# Schematic_v24.net
KiCad netlist of a schematic drawn in EAGLE
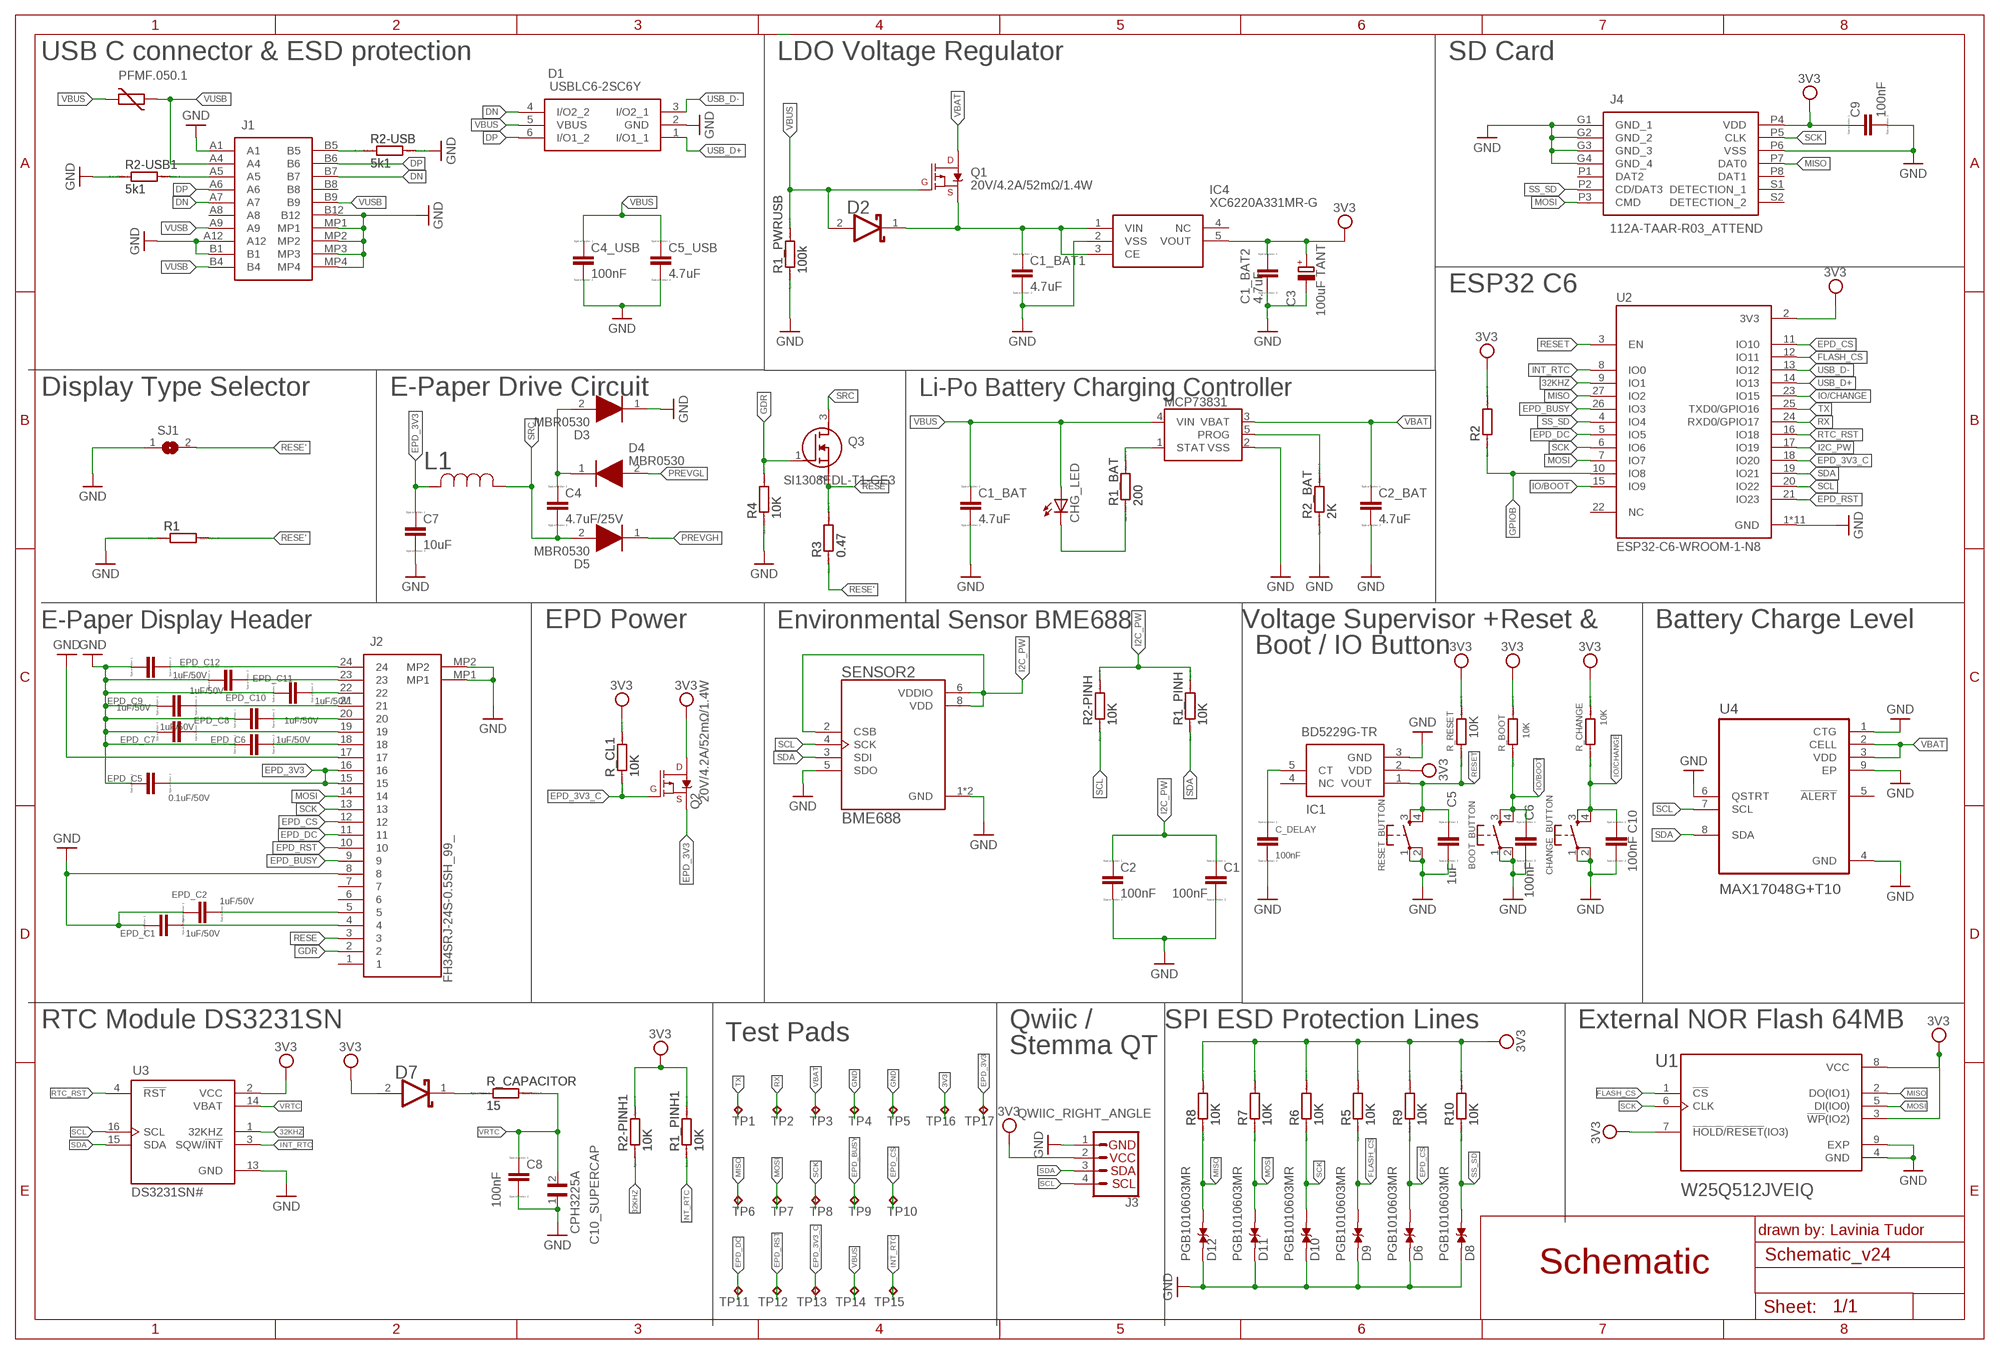
[diagram p0: schematic, sheet 1]

(export (version "E")
  (design (tool "Eeschema 10.0.6"))
  (components
    (comp (ref "BOOT_BUTTON")
      (value "BUTTON_CUSYOMV1")
      (footprint "eagle-import:MYBUTTON")
      (libsource (lib "eagle-import") (part "BUTTON_CUSYOMV1"))
    )
    (comp (ref "C1")
      (value "100nF")
      (footprint "eagle-import:ESP32_WROVER_EAGLE-LTSPICE_C0402")
      (libsource (lib "eagle-import") (part "ESP32_WROVER_EAGLE-LTSPICE_CC0402"))
    )
    (comp (ref "C1_BAT")
      (value "4.7uF")
      (footprint "eagle-import:ESP32_WROVER_EAGLE-LTSPICE_C0402")
      (libsource (lib "eagle-import") (part "ESP32_WROVER_EAGLE-LTSPICE_CC0402"))
    )
    (comp (ref "C1_BAT1")
      (value "4.7uF")
      (footprint "eagle-import:ESP32_WROVER_EAGLE-LTSPICE_C0402")
      (libsource (lib "eagle-import") (part "ESP32_WROVER_EAGLE-LTSPICE_CC0402"))
    )
    (comp (ref "C1_BAT2")
      (value "4.7uF")
      (footprint "eagle-import:ESP32_WROVER_EAGLE-LTSPICE_C0402")
      (libsource (lib "eagle-import") (part "ESP32_WROVER_EAGLE-LTSPICE_CC0402"))
    )
    (comp (ref "C2")
      (value "100nF")
      (footprint "eagle-import:ESP32_WROVER_EAGLE-LTSPICE_C0402")
      (libsource (lib "eagle-import") (part "ESP32_WROVER_EAGLE-LTSPICE_CC0402"))
    )
    (comp (ref "C2_BAT")
      (value "4.7uF")
      (footprint "eagle-import:ESP32_WROVER_EAGLE-LTSPICE_C0402")
      (libsource (lib "eagle-import") (part "ESP32_WROVER_EAGLE-LTSPICE_CC0402"))
    )
    (comp (ref "C3")
      (value "100uF TANT")
      (footprint "eagle-import:RCL_CT3528")
      (libsource (lib "eagle-import") (part "RCL_CPOL-EUCT3528"))
    )
    (comp (ref "C4")
      (value "4.7uF/25V")
      (footprint "eagle-import:ESP32_WROVER_EAGLE-LTSPICE_C0402")
      (libsource (lib "eagle-import") (part "ESP32_WROVER_EAGLE-LTSPICE_CC0402"))
    )
    (comp (ref "C4_USB")
      (value "100nF")
      (footprint "eagle-import:EAGLE-LTSPICE_C0402")
      (libsource (lib "eagle-import") (part "EAGLE-LTSPICE_CC0402"))
    )
    (comp (ref "C5")
      (value "1uF")
      (footprint "eagle-import:ESP32_WROVER_EAGLE-LTSPICE_C0402")
      (libsource (lib "eagle-import") (part "ESP32_WROVER_EAGLE-LTSPICE_CC0402"))
    )
    (comp (ref "C5_USB")
      (value "4.7uF")
      (footprint "eagle-import:EAGLE-LTSPICE_C0402")
      (libsource (lib "eagle-import") (part "EAGLE-LTSPICE_CC0402"))
    )
    (comp (ref "C6")
      (value "100nF")
      (footprint "eagle-import:ESP32_WROVER_EAGLE-LTSPICE_C0402")
      (libsource (lib "eagle-import") (part "ESP32_WROVER_EAGLE-LTSPICE_CC0402"))
    )
    (comp (ref "C7")
      (value "10uF")
      (footprint "eagle-import:ESP32_WROVER_EAGLE-LTSPICE_C0402")
      (libsource (lib "eagle-import") (part "ESP32_WROVER_EAGLE-LTSPICE_CC0402"))
    )
    (comp (ref "C8")
      (value "100nF")
      (footprint "eagle-import:ESP32_WROVER_EAGLE-LTSPICE_C0402")
      (libsource (lib "eagle-import") (part "ESP32_WROVER_EAGLE-LTSPICE_CC0402"))
    )
    (comp (ref "C9")
      (value "100nF")
      (footprint "eagle-import:EAGLE-LTSPICE_C0402")
      (libsource (lib "eagle-import") (part "EAGLE-LTSPICE_CC0402"))
    )
    (comp (ref "C10")
      (value "100nF")
      (footprint "eagle-import:ESP32_WROVER_EAGLE-LTSPICE_C0402")
      (libsource (lib "eagle-import") (part "ESP32_WROVER_EAGLE-LTSPICE_CC0402"))
    )
    (comp (ref "C10_SUPERCAP")
      (value "CPH3225A")
      (footprint "eagle-import:CAPCP3225X100N")
      (fields (field (name "MF") "Seiko Instruments"))
      (libsource (lib "eagle-import") (part "CPH3225A"))
    )
    (comp (ref "CHANGE_BUTTON")
      (value "BUTTON_CUSYOMV1")
      (footprint "eagle-import:MYBUTTON")
      (libsource (lib "eagle-import") (part "BUTTON_CUSYOMV1"))
    )
    (comp (ref "CHG_LED")
      (value "ADAFRUIT_LEDCHIP-LED0603")
      (footprint "eagle-import:ADAFRUIT_CHIP-LED0603")
      (libsource (lib "eagle-import") (part "ADAFRUIT_LEDCHIP-LED0603"))
    )
    (comp (ref "C_DELAY")
      (value "100nF")
      (footprint "eagle-import:ESP32_WROVER_EAGLE-LTSPICE_C0402")
      (libsource (lib "eagle-import") (part "ESP32_WROVER_EAGLE-LTSPICE_CC0402"))
    )
    (comp (ref "D1")
      (value "USBLC6-2SC6Y")
      (footprint "eagle-import:SOT95P280X145-6N")
      (fields (field (name "MF") "STMicroelectronics"))
      (libsource (lib "eagle-import") (part "USBLC6-2SC6Y"))
    )
    (comp (ref "D2")
      (value "ESP32_WROVER_AVX---SD0805S020S1R0_AVX_SD0805S020S1R0_0_0AVX_SD0805S020S1R0_0_0")
      (footprint "eagle-import:ESP32_WROVER_AVX---SD0805S020S1R0_AVX_SD0805S020S1R0_0")
      (fields
        (field (name "DIGIKEY_PART_NUMBER") "478-7800-1-ND")
        (field (name "MF") "AVX")
        (field (name "MOUSER_PART_NUMBER") "581-SD0805S020S1R0")
      )
      (libsource (lib "eagle-import") (part "ESP32_WROVER_AVX---SD0805S020S1R0_AVX_SD0805S020S1R0_0_0AVX_SD0805S020S1R0_0_0"))
    )
    (comp (ref "D3")
      (value "MBR0530")
      (footprint "eagle-import:SOD3716X135N")
      (fields (field (name "MF") "ON Semiconductor"))
      (libsource (lib "eagle-import") (part "MBR0530"))
    )
    (comp (ref "D4")
      (value "MBR0530")
      (footprint "eagle-import:SOD3716X135N")
      (fields (field (name "MF") "ON Semiconductor"))
      (libsource (lib "eagle-import") (part "MBR0530"))
    )
    (comp (ref "D5")
      (value "MBR0530")
      (footprint "eagle-import:SOD3716X135N")
      (fields (field (name "MF") "ON Semiconductor"))
      (libsource (lib "eagle-import") (part "MBR0530"))
    )
    (comp (ref "D6")
      (value "PGB1010603MR")
      (footprint "eagle-import:DIOC1608X36N")
      (fields (field (name "MF") "Littelfuse Inc."))
      (libsource (lib "eagle-import") (part "PGB1010603MR"))
    )
    (comp (ref "D7")
      (value "ESP32_WROVER_AVX---SD0805S020S1R0_AVX_SD0805S020S1R0_0_0AVX_SD0805S020S1R0_0_0")
      (footprint "eagle-import:ESP32_WROVER_AVX---SD0805S020S1R0_AVX_SD0805S020S1R0_0")
      (fields
        (field (name "DIGIKEY_PART_NUMBER") "478-7800-1-ND")
        (field (name "MF") "AVX")
        (field (name "MOUSER_PART_NUMBER") "581-SD0805S020S1R0")
      )
      (libsource (lib "eagle-import") (part "ESP32_WROVER_AVX---SD0805S020S1R0_AVX_SD0805S020S1R0_0_0AVX_SD0805S020S1R0_0_0"))
    )
    (comp (ref "D8")
      (value "PGB1010603MR")
      (footprint "eagle-import:DIOC1608X36N")
      (fields (field (name "MF") "Littelfuse Inc."))
      (libsource (lib "eagle-import") (part "PGB1010603MR"))
    )
    (comp (ref "D9")
      (value "PGB1010603MR")
      (footprint "eagle-import:DIOC1608X36N")
      (fields (field (name "MF") "Littelfuse Inc."))
      (libsource (lib "eagle-import") (part "PGB1010603MR"))
    )
    (comp (ref "D10")
      (value "PGB1010603MR")
      (footprint "eagle-import:DIOC1608X36N")
      (fields (field (name "MF") "Littelfuse Inc."))
      (libsource (lib "eagle-import") (part "PGB1010603MR"))
    )
    (comp (ref "D11")
      (value "PGB1010603MR")
      (footprint "eagle-import:DIOC1608X36N")
      (fields (field (name "MF") "Littelfuse Inc."))
      (libsource (lib "eagle-import") (part "PGB1010603MR"))
    )
    (comp (ref "D12")
      (value "PGB1010603MR")
      (footprint "eagle-import:DIOC1608X36N")
      (fields (field (name "MF") "Littelfuse Inc."))
      (libsource (lib "eagle-import") (part "PGB1010603MR"))
    )
    (comp (ref "EPD_C1")
      (value "1uF/50V")
      (footprint "eagle-import:ESP32_WROVER_EAGLE-LTSPICE_C0402")
      (libsource (lib "eagle-import") (part "ESP32_WROVER_EAGLE-LTSPICE_CC0402"))
    )
    (comp (ref "EPD_C2")
      (value "1uF/50V")
      (footprint "eagle-import:ESP32_WROVER_EAGLE-LTSPICE_C0402")
      (libsource (lib "eagle-import") (part "ESP32_WROVER_EAGLE-LTSPICE_CC0402"))
    )
    (comp (ref "EPD_C5")
      (value "0.1uF/50V")
      (footprint "eagle-import:ESP32_WROVER_EAGLE-LTSPICE_C0402")
      (libsource (lib "eagle-import") (part "ESP32_WROVER_EAGLE-LTSPICE_CC0402"))
    )
    (comp (ref "EPD_C6")
      (value "1uF/50V")
      (footprint "eagle-import:ESP32_WROVER_EAGLE-LTSPICE_C0402")
      (libsource (lib "eagle-import") (part "ESP32_WROVER_EAGLE-LTSPICE_CC0402"))
    )
    (comp (ref "EPD_C7")
      (value "1uF/50V")
      (footprint "eagle-import:ESP32_WROVER_EAGLE-LTSPICE_C0402")
      (libsource (lib "eagle-import") (part "ESP32_WROVER_EAGLE-LTSPICE_CC0402"))
    )
    (comp (ref "EPD_C8")
      (value "1uF/50V")
      (footprint "eagle-import:ESP32_WROVER_EAGLE-LTSPICE_C0402")
      (libsource (lib "eagle-import") (part "ESP32_WROVER_EAGLE-LTSPICE_CC0402"))
    )
    (comp (ref "EPD_C9")
      (value "1uF/50V")
      (footprint "eagle-import:ESP32_WROVER_EAGLE-LTSPICE_C0402")
      (libsource (lib "eagle-import") (part "ESP32_WROVER_EAGLE-LTSPICE_CC0402"))
    )
    (comp (ref "EPD_C10")
      (value "1uF/50V")
      (footprint "eagle-import:ESP32_WROVER_EAGLE-LTSPICE_C0402")
      (libsource (lib "eagle-import") (part "ESP32_WROVER_EAGLE-LTSPICE_CC0402"))
    )
    (comp (ref "EPD_C11")
      (value "1uF/50V")
      (footprint "eagle-import:ESP32_WROVER_EAGLE-LTSPICE_C0402")
      (libsource (lib "eagle-import") (part "ESP32_WROVER_EAGLE-LTSPICE_CC0402"))
    )
    (comp (ref "EPD_C12")
      (value "1uF/50V")
      (footprint "eagle-import:ESP32_WROVER_EAGLE-LTSPICE_C0402")
      (libsource (lib "eagle-import") (part "ESP32_WROVER_EAGLE-LTSPICE_CC0402"))
    )
    (comp (ref "IC1")
      (value "BD5229G-TR")
      (footprint "eagle-import:SOT95P280X125-5N")
      (fields (field (name "MOUSER_PART_NUMBER") "755-BD5229G-TR"))
      (libsource (lib "eagle-import") (part "BD5229G-TR"))
    )
    (comp (ref "IC4")
      (value "XC6220A331MR-G")
      (footprint "eagle-import:SOT95P280X120-5N")
      (fields (field (name "MOUSER_PART_NUMBER") "865-XC6220A331MR-G"))
      (libsource (lib "eagle-import") (part "XC6220A331MR-G"))
    )
    (comp (ref "J1")
      (value "SAMACSYS_PARTS_USB4110-GF-A")
      (footprint "eagle-import:SAMACSYS_PARTS_USB4110GFA")
      (fields
        (field (name "MANUFACTURER_PART_NUMBER") "USB4110-GF-A")
        (field (name "MOUSER_PART_NUMBER") "640-USB4110-GF-A")
      )
      (libsource (lib "eagle-import") (part "SAMACSYS_PARTS_USB4110-GF-A"))
    )
    (comp (ref "J2")
      (value "FH34SRJ-24S-0.5SH_99_")
      (footprint "eagle-import:FH34SRJ24S05SH99")
      (fields
        (field (name "MANUFACTURER_PART_NUMBER") "FH34SRJ-24S-0.5SH(99)")
        (field (name "MOUSER_PART_NUMBER") "798-FH34SRJ24S05SH99")
      )
      (libsource (lib "eagle-import") (part "FH34SRJ-24S-0.5SH_99_"))
    )
    (comp (ref "J3")
      (value "QWIIC_RIGHT_ANGLE")
      (footprint "eagle-import:JST04_1MM_RA")
      (libsource (lib "eagle-import") (part "QWIIC_CONNECTORJS-1MM"))
    )
    (comp (ref "J4")
      (value "112A-TAAR-R03_ATTEND")
      (footprint "eagle-import:112ATAARR03ATTEND")
      (fields (field (name "MANUFACTURER_PART_NUMBER") "112A-TAAR-R03 ATTEND"))
      (libsource (lib "eagle-import") (part "112A-TAAR-R03_ATTEND"))
    )
    (comp (ref "L1")
      (value "744043680IND_4828-WE-TPC_WRE")
      (footprint "eagle-import:IND_4828-WE-TPC_WRE")
      (fields
        (field (name "MANUFACTURER_PART_NUMBER") "744043680")
        (field (name "COPYRIGHT") "Copyright (C) 2024 Ultra Librarian. All rights reserved.")
      )
      (libsource (lib "eagle-import") (part "744043680IND_4828-WE-TPC_WRE"))
    )
    (comp (ref "MCP73831")
      (value "ESP32_WROVER_SPARKFUN-IC-POWER_MCP73831")
      (footprint "eagle-import:ESP32_WROVER_SPARKFUN-IC-POWER_SOT23-5")
      (libsource (lib "eagle-import") (part "ESP32_WROVER_SPARKFUN-IC-POWER_MCP73831"))
    )
    (comp (ref "PFMF.050.1")
      (value "ESP32C6_VARISTORCN1812")
      (footprint "eagle-import:ESP32C6_VARISTOR_CT_CN1812")
      (libsource (lib "eagle-import") (part "ESP32C6_VARISTORCN1812"))
    )
    (comp (ref "Q1")
      (value "20V/4.2A/52mΩ/1.4W")
      (footprint "eagle-import:ESP32_WROVER_SPARKFUN-DISCRETESEMI_SOT23-3")
      (libsource (lib "eagle-import") (part "ESP32_WROVER_SPARKFUN-DISCRETESEMI_MOSFET_PCH-DMG2305UX-7"))
    )
    (comp (ref "Q2")
      (value "20V/4.2A/52mΩ/1.4W")
      (footprint "eagle-import:ESP32_WROVER_SPARKFUN-DISCRETESEMI_SOT23-3")
      (libsource (lib "eagle-import") (part "ESP32_WROVER_SPARKFUN-DISCRETESEMI_MOSFET_PCH-DMG2305UX-7"))
    )
    (comp (ref "Q3")
      (value "SI1308EDL-T1-GE3")
      (footprint "eagle-import:SOT65P210X110-3N")
      (fields (field (name "MF") "Vishay Siliconix"))
      (libsource (lib "eagle-import") (part "SI1308EDL-T1-GE3"))
    )
    (comp (ref "R1")
      (value "ESP32_WROVER_EAGLE-LTSPICE_RR0402")
      (footprint "eagle-import:ESP32_WROVER_EAGLE-LTSPICE_R0402")
      (libsource (lib "eagle-import") (part "ESP32_WROVER_EAGLE-LTSPICE_RR0402"))
    )
    (comp (ref "R1_BAT")
      (value "200")
      (footprint "eagle-import:ESP32_WROVER_EAGLE-LTSPICE_R0402")
      (libsource (lib "eagle-import") (part "ESP32_WROVER_EAGLE-LTSPICE_RR0402"))
    )
    (comp (ref "R1_PINH")
      (value "10K")
      (footprint "eagle-import:ESP32_WROVER_EAGLE-LTSPICE_R0402")
      (libsource (lib "eagle-import") (part "ESP32_WROVER_EAGLE-LTSPICE_RR0402"))
    )
    (comp (ref "R1_PINH1")
      (value "10K")
      (footprint "eagle-import:ESP32_WROVER_EAGLE-LTSPICE_R0402")
      (libsource (lib "eagle-import") (part "ESP32_WROVER_EAGLE-LTSPICE_RR0402"))
    )
    (comp (ref "R1_PWRUSB")
      (value "100k")
      (footprint "eagle-import:ESP32_WROVER_EAGLE-LTSPICE_R0402")
      (libsource (lib "eagle-import") (part "ESP32_WROVER_EAGLE-LTSPICE_RR0402"))
    )
    (comp (ref "R2")
      (value "ESP32_WROVER_EAGLE-LTSPICE_RR0402")
      (footprint "eagle-import:ESP32_WROVER_EAGLE-LTSPICE_R0402")
      (libsource (lib "eagle-import") (part "ESP32_WROVER_EAGLE-LTSPICE_RR0402"))
    )
    (comp (ref "R2-PINH")
      (value "10K")
      (footprint "eagle-import:ESP32_WROVER_EAGLE-LTSPICE_R0402")
      (libsource (lib "eagle-import") (part "ESP32_WROVER_EAGLE-LTSPICE_RR0402"))
    )
    (comp (ref "R2-PINH1")
      (value "10K")
      (footprint "eagle-import:ESP32_WROVER_EAGLE-LTSPICE_R0402")
      (libsource (lib "eagle-import") (part "ESP32_WROVER_EAGLE-LTSPICE_RR0402"))
    )
    (comp (ref "R2-USB")
      (value "5k1")
      (footprint "eagle-import:ESP32_WROVER_EAGLE-LTSPICE_R0402")
      (libsource (lib "eagle-import") (part "ESP32_WROVER_EAGLE-LTSPICE_RR0402"))
    )
    (comp (ref "R2-USB1")
      (value "5k1")
      (footprint "eagle-import:ESP32_WROVER_EAGLE-LTSPICE_R0402")
      (libsource (lib "eagle-import") (part "ESP32_WROVER_EAGLE-LTSPICE_RR0402"))
    )
    (comp (ref "R2_BAT")
      (value "2K")
      (footprint "eagle-import:ESP32_WROVER_EAGLE-LTSPICE_R0402")
      (libsource (lib "eagle-import") (part "ESP32_WROVER_EAGLE-LTSPICE_RR0402"))
    )
    (comp (ref "R3")
      (value "0.47")
      (footprint "eagle-import:ESP32_WROVER_EAGLE-LTSPICE_R0402")
      (libsource (lib "eagle-import") (part "ESP32_WROVER_EAGLE-LTSPICE_RR0402"))
    )
    (comp (ref "R4")
      (value "10K")
      (footprint "eagle-import:ESP32_WROVER_EAGLE-LTSPICE_R0402")
      (libsource (lib "eagle-import") (part "ESP32_WROVER_EAGLE-LTSPICE_RR0402"))
    )
    (comp (ref "R5")
      (value "10K")
      (footprint "eagle-import:ESP32_WROVER_EAGLE-LTSPICE_R0402")
      (libsource (lib "eagle-import") (part "ESP32_WROVER_EAGLE-LTSPICE_RR0402"))
    )
    (comp (ref "R6")
      (value "10K")
      (footprint "eagle-import:ESP32_WROVER_EAGLE-LTSPICE_R0402")
      (libsource (lib "eagle-import") (part "ESP32_WROVER_EAGLE-LTSPICE_RR0402"))
    )
    (comp (ref "R7")
      (value "10K")
      (footprint "eagle-import:ESP32_WROVER_EAGLE-LTSPICE_R0402")
      (libsource (lib "eagle-import") (part "ESP32_WROVER_EAGLE-LTSPICE_RR0402"))
    )
    (comp (ref "R8")
      (value "10K")
      (footprint "eagle-import:ESP32_WROVER_EAGLE-LTSPICE_R0402")
      (libsource (lib "eagle-import") (part "ESP32_WROVER_EAGLE-LTSPICE_RR0402"))
    )
    (comp (ref "R9")
      (value "10K")
      (footprint "eagle-import:ESP32_WROVER_EAGLE-LTSPICE_R0402")
      (libsource (lib "eagle-import") (part "ESP32_WROVER_EAGLE-LTSPICE_RR0402"))
    )
    (comp (ref "R10")
      (value "10K")
      (footprint "eagle-import:ESP32_WROVER_EAGLE-LTSPICE_R0402")
      (libsource (lib "eagle-import") (part "ESP32_WROVER_EAGLE-LTSPICE_RR0402"))
    )
    (comp (ref "RESET_BUTTON")
      (value "BUTTON_CUSYOMV1")
      (footprint "eagle-import:MYBUTTON")
      (libsource (lib "eagle-import") (part "BUTTON_CUSYOMV1"))
    )
    (comp (ref "R_BOOT")
      (value "10K")
      (footprint "eagle-import:ESP32_WROVER_EAGLE-LTSPICE_R0402")
      (libsource (lib "eagle-import") (part "ESP32_WROVER_EAGLE-LTSPICE_RR0402"))
    )
    (comp (ref "R_CAPACITOR")
      (value "15")
      (footprint "eagle-import:ESP32_WROVER_EAGLE-LTSPICE_R0402")
      (libsource (lib "eagle-import") (part "ESP32_WROVER_EAGLE-LTSPICE_RR0402"))
    )
    (comp (ref "R_CHANGE")
      (value "10K")
      (footprint "eagle-import:ESP32_WROVER_EAGLE-LTSPICE_R0402")
      (libsource (lib "eagle-import") (part "ESP32_WROVER_EAGLE-LTSPICE_RR0402"))
    )
    (comp (ref "R_CL1")
      (value "10K")
      (footprint "eagle-import:ESP32_WROVER_EAGLE-LTSPICE_R0402")
      (libsource (lib "eagle-import") (part "ESP32_WROVER_EAGLE-LTSPICE_RR0402"))
    )
    (comp (ref "R_RESET")
      (value "10K")
      (footprint "eagle-import:ESP32_WROVER_EAGLE-LTSPICE_R0402")
      (libsource (lib "eagle-import") (part "ESP32_WROVER_EAGLE-LTSPICE_RR0402"))
    )
    (comp (ref "SENSOR2")
      (value "BME688")
      (footprint "eagle-import:ESP32_WROVER_BME680_PSON80P300X300X100-8N")
      (fields (field (name "MF") "Bosch Sensortec") (field (name "MP") "BME680"))
      (libsource (lib "eagle-import") (part "ESP32_WROVER_BME680_BME680"))
    )
    (comp (ref "SJ1") (value "SJ") (footprint "eagle-import:SJ") (libsource (lib "eagle-import") (part "SJ")))
    (comp (ref "TP1")
      (value "TPTP20R")
      (footprint "eagle-import:TP20R")
      (libsource (lib "eagle-import") (part "TPTP20R"))
    )
    (comp (ref "TP2")
      (value "TPTP20R")
      (footprint "eagle-import:TP20R")
      (libsource (lib "eagle-import") (part "TPTP20R"))
    )
    (comp (ref "TP3")
      (value "TPTP20R")
      (footprint "eagle-import:TP20R")
      (libsource (lib "eagle-import") (part "TPTP20R"))
    )
    (comp (ref "TP4")
      (value "TPTP20R")
      (footprint "eagle-import:TP20R")
      (libsource (lib "eagle-import") (part "TPTP20R"))
    )
    (comp (ref "TP5")
      (value "TPTP20R")
      (footprint "eagle-import:TP20R")
      (libsource (lib "eagle-import") (part "TPTP20R"))
    )
    (comp (ref "TP6")
      (value "TPTP20R")
      (footprint "eagle-import:TP20R")
      (libsource (lib "eagle-import") (part "TPTP20R"))
    )
    (comp (ref "TP7")
      (value "TPTP20R")
      (footprint "eagle-import:TP20R")
      (libsource (lib "eagle-import") (part "TPTP20R"))
    )
    (comp (ref "TP8")
      (value "TPTP20R")
      (footprint "eagle-import:TP20R")
      (libsource (lib "eagle-import") (part "TPTP20R"))
    )
    (comp (ref "TP9")
      (value "TPTP20R")
      (footprint "eagle-import:TP20R")
      (libsource (lib "eagle-import") (part "TPTP20R"))
    )
    (comp (ref "TP10")
      (value "TPTP20R")
      (footprint "eagle-import:TP20R")
      (libsource (lib "eagle-import") (part "TPTP20R"))
    )
    (comp (ref "TP11")
      (value "TPTP20R")
      (footprint "eagle-import:TP20R")
      (libsource (lib "eagle-import") (part "TPTP20R"))
    )
    (comp (ref "TP12")
      (value "TPTP20R")
      (footprint "eagle-import:TP20R")
      (libsource (lib "eagle-import") (part "TPTP20R"))
    )
    (comp (ref "TP13")
      (value "TPTP20R")
      (footprint "eagle-import:TP20R")
      (libsource (lib "eagle-import") (part "TPTP20R"))
    )
    (comp (ref "TP14")
      (value "TPTP20R")
      (footprint "eagle-import:TP20R")
      (libsource (lib "eagle-import") (part "TPTP20R"))
    )
    (comp (ref "TP15")
      (value "TPTP20R")
      (footprint "eagle-import:TP20R")
      (libsource (lib "eagle-import") (part "TPTP20R"))
    )
    (comp (ref "TP16")
      (value "TPTP20R")
      (footprint "eagle-import:TP20R")
      (libsource (lib "eagle-import") (part "TPTP20R"))
    )
    (comp (ref "TP17")
      (value "TPTP20R")
      (footprint "eagle-import:TP20R")
      (libsource (lib "eagle-import") (part "TPTP20R"))
    )
    (comp (ref "U1")
      (value "W25Q512JVEIQ")
      (footprint "eagle-import:SON127P600X800X80-9N")
      (fields (field (name "MF") "Winbond Electronics"))
      (libsource (lib "eagle-import") (part "W25Q512JVEIQ"))
    )
    (comp (ref "U2")
      (value "ESP32-C6-WROOM-1-N8")
      (footprint "eagle-import:XCVR_ESP32-C6-WROOM-1-N8")
      (fields (field (name "MF") "Espressif Systems"))
      (libsource (lib "eagle-import") (part "ESP32-C6-WROOM-1-N8"))
    )
    (comp (ref "U3")
      (value "DS3231SN#")
      (footprint "eagle-import:SOIC127P1032X265-16N")
      (fields (field (name "MF") "Analog Devices"))
      (libsource (lib "eagle-import") (part "DS3231SN#"))
    )
    (comp (ref "U4")
      (value "MAX17048G+T10")
      (footprint "eagle-import:SON50P200X200X80-9N")
      (fields (field (name "MF") "Analog Devices"))
      (libsource (lib "eagle-import") (part "MAX17048G+T10"))
    )
  )
  (nets
    (net (code "1") (name "3V3") (class "Default")
      (node (ref "C1_BAT2") (pin "1") (pinfunction "1_1") (pintype "passive"))
      (node (ref "C3") (pin "+") (pinfunction "+_+") (pintype "passive"))
      (node (ref "C9") (pin "1") (pinfunction "1_1") (pintype "passive"))
      (node (ref "D7") (pin "2") (pinfunction "ANODE_2") (pintype "bidirectional"))
      (node (ref "IC1") (pin "2") (pinfunction "VDD_2") (pintype "bidirectional"))
      (node (ref "IC4") (pin "5") (pinfunction "VOUT_5") (pintype "bidirectional"))
      (node (ref "J3") (pin "2") (pinfunction "2_2") (pintype "power_in"))
      (node (ref "J4") (pin "P4") (pinfunction "VDD_P4") (pintype "bidirectional"))
      (node (ref "Q2") (pin "3") (pinfunction "D_3") (pintype "bidirectional"))
      (node (ref "R10") (pin "2") (pinfunction "2_2") (pintype "passive"))
      (node (ref "R1_PINH1") (pin "2") (pinfunction "2_2") (pintype "passive"))
      (node (ref "R2") (pin "2") (pinfunction "2_2") (pintype "passive"))
      (node (ref "R2-PINH1") (pin "2") (pinfunction "2_2") (pintype "passive"))
      (node (ref "R5") (pin "2") (pinfunction "2_2") (pintype "passive"))
      (node (ref "R6") (pin "2") (pinfunction "2_2") (pintype "passive"))
      (node (ref "R7") (pin "2") (pinfunction "2_2") (pintype "passive"))
      (node (ref "R8") (pin "2") (pinfunction "2_2") (pintype "passive"))
      (node (ref "R9") (pin "2") (pinfunction "2_2") (pintype "passive"))
      (node (ref "R_BOOT") (pin "2") (pinfunction "2_2") (pintype "passive"))
      (node (ref "R_CHANGE") (pin "2") (pinfunction "2_2") (pintype "passive"))
      (node (ref "R_CL1") (pin "2") (pinfunction "2_2") (pintype "passive"))
      (node (ref "R_RESET") (pin "2") (pinfunction "2_2") (pintype "passive"))
      (node (ref "TP16") (pin "TP") (pinfunction "TP_TP") (pintype "input"))
      (node (ref "U1") (pin "3") (pinfunction "~{WP}(IO2)_3") (pintype "bidirectional"))
      (node (ref "U1") (pin "7") (pinfunction "~{HOLD}/~{RESET}(IO3)_7") (pintype "bidirectional"))
      (node (ref "U1") (pin "8") (pinfunction "VCC_8") (pintype "power_in"))
      (node (ref "U2") (pin "2") (pinfunction "3V3_2") (pintype "power_in"))
      (node (ref "U3") (pin "2") (pinfunction "VCC_2") (pintype "power_in"))
    )
    (net (code "2") (name "32KHZ") (class "Default")
      (node (ref "R2-PINH1") (pin "1") (pinfunction "1_1") (pintype "passive"))
      (node (ref "U2") (pin "9") (pinfunction "IO1_9") (pintype "bidirectional"))
      (node (ref "U3") (pin "1") (pinfunction "32KHZ_1") (pintype "output"))
    )
    (net (code "3") (name "DN") (class "Default")
      (node (ref "D1") (pin "4") (pinfunction "I/O2_2_4") (pintype "bidirectional"))
      (node (ref "J1") (pin "A7") (pinfunction "A7_A7") (pintype "bidirectional"))
      (node (ref "J1") (pin "B7") (pinfunction "B7_B7") (pintype "bidirectional"))
    )
    (net (code "4") (name "DP") (class "Default")
      (node (ref "D1") (pin "6") (pinfunction "I/O1_2_6") (pintype "bidirectional"))
      (node (ref "J1") (pin "A6") (pinfunction "A6_A6") (pintype "bidirectional"))
      (node (ref "J1") (pin "B6") (pinfunction "B6_B6") (pintype "bidirectional"))
    )
    (net (code "5") (name "EPD_3V3") (class "Default")
      (node (ref "C7") (pin "1") (pinfunction "1_1") (pintype "passive"))
      (node (ref "EPD_C5") (pin "2") (pinfunction "2_2") (pintype "passive"))
      (node (ref "J2") (pin "15") (pinfunction "15_15") (pintype "bidirectional"))
      (node (ref "J2") (pin "16") (pinfunction "16_16") (pintype "bidirectional"))
      (node (ref "L1") (pin "2") (pinfunction "2_2") (pintype "passive"))
      (node (ref "Q2") (pin "2") (pinfunction "S_2") (pintype "bidirectional"))
      (node (ref "TP17") (pin "TP") (pinfunction "TP_TP") (pintype "input"))
    )
    (net (code "6") (name "EPD_3V3_C") (class "Default")
      (node (ref "Q2") (pin "1") (pinfunction "G_1") (pintype "bidirectional"))
      (node (ref "R_CL1") (pin "1") (pinfunction "1_1") (pintype "passive"))
      (node (ref "TP13") (pin "TP") (pinfunction "TP_TP") (pintype "input"))
      (node (ref "U2") (pin "18") (pinfunction "IO20_18") (pintype "bidirectional"))
    )
    (net (code "7") (name "EPD_BUSY") (class "Default")
      (node (ref "J2") (pin "9") (pinfunction "9_9") (pintype "bidirectional"))
      (node (ref "TP9") (pin "TP") (pinfunction "TP_TP") (pintype "input"))
      (node (ref "U2") (pin "26") (pinfunction "IO3_26") (pintype "bidirectional"))
    )
    (net (code "8") (name "EPD_CS") (class "Default")
      (node (ref "D6") (pin "2") (pinfunction "2_2") (pintype "passive"))
      (node (ref "J2") (pin "12") (pinfunction "12_12") (pintype "bidirectional"))
      (node (ref "R9") (pin "1") (pinfunction "1_1") (pintype "passive"))
      (node (ref "TP10") (pin "TP") (pinfunction "TP_TP") (pintype "input"))
      (node (ref "U2") (pin "11") (pinfunction "IO10_11") (pintype "bidirectional"))
    )
    (net (code "9") (name "EPD_DC") (class "Default")
      (node (ref "J2") (pin "11") (pinfunction "11_11") (pintype "bidirectional"))
      (node (ref "TP11") (pin "TP") (pinfunction "TP_TP") (pintype "input"))
      (node (ref "U2") (pin "5") (pinfunction "IO5_5") (pintype "bidirectional"))
    )
    (net (code "10") (name "EPD_RST") (class "Default")
      (node (ref "J2") (pin "10") (pinfunction "10_10") (pintype "bidirectional"))
      (node (ref "TP12") (pin "TP") (pinfunction "TP_TP") (pintype "input"))
      (node (ref "U2") (pin "21") (pinfunction "IO23_21") (pintype "bidirectional"))
    )
    (net (code "11") (name "FLASH_CS") (class "Default")
      (node (ref "D9") (pin "2") (pinfunction "2_2") (pintype "passive"))
      (node (ref "R5") (pin "1") (pinfunction "1_1") (pintype "passive"))
      (node (ref "U1") (pin "1") (pinfunction "~{CS}_1") (pintype "input"))
      (node (ref "U2") (pin "12") (pinfunction "IO11_12") (pintype "bidirectional"))
    )
    (net (code "12") (name "GDR") (class "Default")
      (node (ref "J2") (pin "2") (pinfunction "2_2") (pintype "bidirectional"))
      (node (ref "Q3") (pin "1") (pinfunction "G_1") (pintype "bidirectional"))
      (node (ref "R4") (pin "2") (pinfunction "2_2") (pintype "passive"))
    )
    (net (code "13") (name "GND") (class "Default")
      (node (ref "BOOT_BUTTON") (pin "1") (pinfunction "1_1") (pintype "passive"))
      (node (ref "BOOT_BUTTON") (pin "2") (pinfunction "2_2") (pintype "passive"))
      (node (ref "C1") (pin "2") (pinfunction "2_2") (pintype "passive"))
      (node (ref "C10") (pin "2") (pinfunction "2_2") (pintype "passive"))
      (node (ref "C10_SUPERCAP") (pin "1") (pinfunction "1_1") (pintype "passive"))
      (node (ref "C1_BAT") (pin "2") (pinfunction "2_2") (pintype "passive"))
      (node (ref "C1_BAT1") (pin "2") (pinfunction "2_2") (pintype "passive"))
      (node (ref "C1_BAT2") (pin "2") (pinfunction "2_2") (pintype "passive"))
      (node (ref "C2") (pin "2") (pinfunction "2_2") (pintype "passive"))
      (node (ref "C2_BAT") (pin "2") (pinfunction "2_2") (pintype "passive"))
      (node (ref "C3") (pin "-") (pinfunction "-_-") (pintype "passive"))
      (node (ref "C4_USB") (pin "2") (pinfunction "2_2") (pintype "passive"))
      (node (ref "C5") (pin "2") (pinfunction "2_2") (pintype "passive"))
      (node (ref "C5_USB") (pin "2") (pinfunction "2_2") (pintype "passive"))
      (node (ref "C6") (pin "2") (pinfunction "2_2") (pintype "passive"))
      (node (ref "C7") (pin "2") (pinfunction "2_2") (pintype "passive"))
      (node (ref "C8") (pin "2") (pinfunction "2_2") (pintype "passive"))
      (node (ref "C9") (pin "2") (pinfunction "2_2") (pintype "passive"))
      (node (ref "CHANGE_BUTTON") (pin "1") (pinfunction "1_1") (pintype "passive"))
      (node (ref "CHANGE_BUTTON") (pin "2") (pinfunction "2_2") (pintype "passive"))
      (node (ref "C_DELAY") (pin "2") (pinfunction "2_2") (pintype "passive"))
      (node (ref "D1") (pin "2") (pinfunction "GND_2") (pintype "bidirectional"))
      (node (ref "D10") (pin "1") (pinfunction "1_1") (pintype "passive"))
      (node (ref "D11") (pin "1") (pinfunction "1_1") (pintype "passive"))
      (node (ref "D12") (pin "1") (pinfunction "1_1") (pintype "passive"))
      (node (ref "D3") (pin "1") (pinfunction "K_1") (pintype "bidirectional"))
      (node (ref "D6") (pin "1") (pinfunction "1_1") (pintype "passive"))
      (node (ref "D8") (pin "1") (pinfunction "1_1") (pintype "passive"))
      (node (ref "D9") (pin "1") (pinfunction "1_1") (pintype "passive"))
      (node (ref "EPD_C1") (pin "1") (pinfunction "1_1") (pintype "passive"))
      (node (ref "EPD_C10") (pin "1") (pinfunction "1_1") (pintype "passive"))
      (node (ref "EPD_C11") (pin "1") (pinfunction "1_1") (pintype "passive"))
      (node (ref "EPD_C12") (pin "1") (pinfunction "1_1") (pintype "passive"))
      (node (ref "EPD_C2") (pin "1") (pinfunction "1_1") (pintype "passive"))
      (node (ref "EPD_C5") (pin "1") (pinfunction "1_1") (pintype "passive"))
      (node (ref "EPD_C6") (pin "1") (pinfunction "1_1") (pintype "passive"))
      (node (ref "EPD_C7") (pin "1") (pinfunction "1_1") (pintype "passive"))
      (node (ref "EPD_C8") (pin "1") (pinfunction "1_1") (pintype "passive"))
      (node (ref "EPD_C9") (pin "1") (pinfunction "1_1") (pintype "passive"))
      (node (ref "IC1") (pin "3") (pinfunction "GND_3") (pintype "bidirectional"))
      (node (ref "IC4") (pin "2") (pinfunction "VSS_2") (pintype "bidirectional"))
      (node (ref "J1") (pin "A1") (pinfunction "A1_A1") (pintype "bidirectional"))
      (node (ref "J1") (pin "A12") (pinfunction "A12_A12") (pintype "bidirectional"))
      (node (ref "J1") (pin "B1") (pinfunction "B1_B1") (pintype "bidirectional"))
      (node (ref "J1") (pin "B12") (pinfunction "B12_B12") (pintype "bidirectional"))
      (node (ref "J1") (pin "MP1") (pinfunction "MP1_MP1") (pintype "bidirectional"))
      (node (ref "J1") (pin "MP2") (pinfunction "MP2_MP2") (pintype "bidirectional"))
      (node (ref "J1") (pin "MP3") (pinfunction "MP3_MP3") (pintype "bidirectional"))
      (node (ref "J1") (pin "MP4") (pinfunction "MP4_MP4") (pintype "bidirectional"))
      (node (ref "J2") (pin "17") (pinfunction "17_17") (pintype "bidirectional"))
      (node (ref "J2") (pin "8") (pinfunction "8_8") (pintype "bidirectional"))
      (node (ref "J2") (pin "MP1") (pinfunction "MP1_MP1") (pintype "bidirectional"))
      (node (ref "J2") (pin "MP2") (pinfunction "MP2_MP2") (pintype "bidirectional"))
      (node (ref "J3") (pin "1") (pinfunction "1_1") (pintype "power_in"))
      (node (ref "J4") (pin "G1") (pinfunction "GND_1_G1") (pintype "bidirectional"))
      (node (ref "J4") (pin "G2") (pinfunction "GND_2_G2") (pintype "bidirectional"))
      (node (ref "J4") (pin "G3") (pinfunction "GND_3_G3") (pintype "bidirectional"))
      (node (ref "J4") (pin "G4") (pinfunction "GND_4_G4") (pintype "bidirectional"))
      (node (ref "J4") (pin "P6") (pinfunction "VSS_P6") (pintype "bidirectional"))
      (node (ref "MCP73831") (pin "2") (pinfunction "VSS_2") (pintype "power_in"))
      (node (ref "R1") (pin "1") (pinfunction "1_1") (pintype "passive"))
      (node (ref "R1_PWRUSB") (pin "1") (pinfunction "1_1") (pintype "passive"))
      (node (ref "R2-USB") (pin "2") (pinfunction "2_2") (pintype "passive"))
      (node (ref "R2-USB1") (pin "1") (pinfunction "1_1") (pintype "passive"))
      (node (ref "R2_BAT") (pin "1") (pinfunction "1_1") (pintype "passive"))
      (node (ref "R4") (pin "1") (pinfunction "1_1") (pintype "passive"))
      (node (ref "RESET_BUTTON") (pin "1") (pinfunction "1_1") (pintype "passive"))
      (node (ref "RESET_BUTTON") (pin "2") (pinfunction "2_2") (pintype "passive"))
      (node (ref "SENSOR2") (pin "1") (pinfunction "GND_1") (pintype "power_in"))
      (node (ref "SENSOR2") (pin "5") (pinfunction "SDO_5") (pintype "bidirectional"))
      (node (ref "SENSOR2") (pin "7") (pinfunction "GND_7") (pintype "power_in"))
      (node (ref "SJ1") (pin "1") (pinfunction "1_1") (pintype "passive"))
      (node (ref "TP4") (pin "TP") (pinfunction "TP_TP") (pintype "input"))
      (node (ref "TP5") (pin "TP") (pinfunction "TP_TP") (pintype "input"))
      (node (ref "U1") (pin "4") (pinfunction "GND_4") (pintype "power_in"))
      (node (ref "U1") (pin "9") (pinfunction "EXP_9") (pintype "passive"))
      (node (ref "U2") (pin "1") (pinfunction "GND_1") (pintype "power_in"))
      (node (ref "U2") (pin "28") (pinfunction "GND_28") (pintype "power_in"))
      (node (ref "U2") (pin "29_1") (pinfunction "GND_29_1") (pintype "power_in"))
      (node (ref "U2") (pin "29_2") (pinfunction "GND_29_2") (pintype "power_in"))
      (node (ref "U2") (pin "29_3") (pinfunction "GND_29_3") (pintype "power_in"))
      (node (ref "U2") (pin "29_4") (pinfunction "GND_29_4") (pintype "power_in"))
      (node (ref "U2") (pin "29_5") (pinfunction "GND_29_5") (pintype "power_in"))
      (node (ref "U2") (pin "29_6") (pinfunction "GND_29_6") (pintype "power_in"))
      (node (ref "U2") (pin "29_7") (pinfunction "GND_29_7") (pintype "power_in"))
      (node (ref "U2") (pin "29_8") (pinfunction "GND_29_8") (pintype "power_in"))
      (node (ref "U2") (pin "29_9") (pinfunction "GND_29_9") (pintype "power_in"))
      (node (ref "U3") (pin "13") (pinfunction "GND_13") (pintype "power_in"))
      (node (ref "U4") (pin "1") (pinfunction "CTG_1") (pintype "power_in"))
      (node (ref "U4") (pin "4") (pinfunction "GND_4") (pintype "power_in"))
      (node (ref "U4") (pin "6") (pinfunction "QSTRT_6") (pintype "input"))
      (node (ref "U4") (pin "9") (pinfunction "EP_9") (pintype "power_in"))
    )
    (net (code "14") (name "GPIOB") (class "Default")
      (node (ref "R2") (pin "1") (pinfunction "1_1") (pintype "passive"))
      (node (ref "U2") (pin "10") (pinfunction "IO8_10") (pintype "bidirectional"))
    )
    (net (code "15") (name "I2C_PW") (class "Default")
      (node (ref "C1") (pin "1") (pinfunction "1_1") (pintype "passive"))
      (node (ref "C2") (pin "1") (pinfunction "1_1") (pintype "passive"))
      (node (ref "R1_PINH") (pin "2") (pinfunction "2_2") (pintype "passive"))
      (node (ref "R2-PINH") (pin "2") (pinfunction "2_2") (pintype "passive"))
      (node (ref "SENSOR2") (pin "2") (pinfunction "CSB_2") (pintype "input"))
      (node (ref "SENSOR2") (pin "6") (pinfunction "VDDIO_6") (pintype "power_in"))
      (node (ref "SENSOR2") (pin "8") (pinfunction "VDD_8") (pintype "power_in"))
      (node (ref "U2") (pin "17") (pinfunction "IO19_17") (pintype "bidirectional"))
    )
    (net (code "16") (name "INT_RTC") (class "Default")
      (node (ref "R1_PINH1") (pin "1") (pinfunction "1_1") (pintype "passive"))
      (node (ref "TP15") (pin "TP") (pinfunction "TP_TP") (pintype "input"))
      (node (ref "U2") (pin "8") (pinfunction "IO0_8") (pintype "bidirectional"))
      (node (ref "U3") (pin "3") (pinfunction "SQW/~{INT}_3") (pintype "output"))
    )
    (net (code "17") (name "IO{slash}BOOT") (class "Default")
      (node (ref "BOOT_BUTTON") (pin "3") (pinfunction "3_3") (pintype "passive"))
      (node (ref "BOOT_BUTTON") (pin "4") (pinfunction "4_4") (pintype "passive"))
      (node (ref "C6") (pin "1") (pinfunction "1_1") (pintype "passive"))
      (node (ref "R_BOOT") (pin "1") (pinfunction "1_1") (pintype "passive"))
      (node (ref "U2") (pin "15") (pinfunction "IO9_15") (pintype "bidirectional"))
    )
    (net (code "18") (name "IO{slash}CHANGE") (class "Default")
      (node (ref "C10") (pin "1") (pinfunction "1_1") (pintype "passive"))
      (node (ref "CHANGE_BUTTON") (pin "3") (pinfunction "3_3") (pintype "passive"))
      (node (ref "CHANGE_BUTTON") (pin "4") (pinfunction "4_4") (pintype "passive"))
      (node (ref "R_CHANGE") (pin "1") (pinfunction "1_1") (pintype "passive"))
      (node (ref "U2") (pin "23") (pinfunction "IO15_23") (pintype "bidirectional"))
    )
    (net (code "19") (name "MISO") (class "Default")
      (node (ref "D12") (pin "2") (pinfunction "2_2") (pintype "passive"))
      (node (ref "J4") (pin "P7") (pinfunction "DAT0_P7") (pintype "bidirectional"))
      (node (ref "R8") (pin "1") (pinfunction "1_1") (pintype "passive"))
      (node (ref "TP6") (pin "TP") (pinfunction "TP_TP") (pintype "input"))
      (node (ref "U1") (pin "2") (pinfunction "DO(IO1)_2") (pintype "bidirectional"))
      (node (ref "U2") (pin "27") (pinfunction "IO2_27") (pintype "bidirectional"))
    )
    (net (code "20") (name "MOSI") (class "Default")
      (node (ref "D11") (pin "2") (pinfunction "2_2") (pintype "passive"))
      (node (ref "J2") (pin "14") (pinfunction "14_14") (pintype "bidirectional"))
      (node (ref "J4") (pin "P3") (pinfunction "CMD_P3") (pintype "bidirectional"))
      (node (ref "R7") (pin "1") (pinfunction "1_1") (pintype "passive"))
      (node (ref "TP7") (pin "TP") (pinfunction "TP_TP") (pintype "input"))
      (node (ref "U1") (pin "5") (pinfunction "DI(IO0)_5") (pintype "bidirectional"))
      (node (ref "U2") (pin "7") (pinfunction "IO7_7") (pintype "bidirectional"))
    )
    (net (code "21") (name "Net-(CHG_LED-PadC)") (class "Default")
      (node (ref "CHG_LED") (pin "C") (pinfunction "C_C") (pintype "passive"))
      (node (ref "R1_BAT") (pin "1") (pinfunction "1_1") (pintype "passive"))
    )
    (net (code "22") (name "Net-(D2-CATHODE)") (class "Default")
      (node (ref "C1_BAT1") (pin "1") (pinfunction "1_1") (pintype "passive"))
      (node (ref "D2") (pin "1") (pinfunction "CATHODE_1") (pintype "bidirectional"))
      (node (ref "IC4") (pin "1") (pinfunction "VIN_1") (pintype "bidirectional"))
      (node (ref "IC4") (pin "3") (pinfunction "CE_3") (pintype "bidirectional"))
      (node (ref "Q1") (pin "2") (pinfunction "S_2") (pintype "bidirectional"))
    )
    (net (code "23") (name "Net-(D3-A)") (class "Default")
      (node (ref "C4") (pin "1") (pinfunction "1_1") (pintype "passive"))
      (node (ref "D3") (pin "2") (pinfunction "A_2") (pintype "bidirectional"))
      (node (ref "D4") (pin "1") (pinfunction "K_1") (pintype "bidirectional"))
    )
    (net (code "24") (name "Net-(D7-CATHODE)") (class "Default")
      (node (ref "D7") (pin "1") (pinfunction "CATHODE_1") (pintype "bidirectional"))
      (node (ref "R_CAPACITOR") (pin "1") (pinfunction "1_1") (pintype "passive"))
    )
    (net (code "25") (name "Net-(EPD_C1-Pad2)") (class "Default")
      (node (ref "EPD_C1") (pin "2") (pinfunction "2_2") (pintype "passive"))
      (node (ref "J2") (pin "4") (pinfunction "4_4") (pintype "bidirectional"))
    )
    (net (code "26") (name "Net-(EPD_C2-Pad2)") (class "Default")
      (node (ref "EPD_C2") (pin "2") (pinfunction "2_2") (pintype "passive"))
      (node (ref "J2") (pin "5") (pinfunction "5_5") (pintype "bidirectional"))
    )
    (net (code "27") (name "Net-(EPD_C6-Pad2)") (class "Default")
      (node (ref "EPD_C6") (pin "2") (pinfunction "2_2") (pintype "passive"))
      (node (ref "J2") (pin "18") (pinfunction "18_18") (pintype "bidirectional"))
    )
    (net (code "28") (name "Net-(EPD_C7-Pad2)") (class "Default")
      (node (ref "EPD_C7") (pin "2") (pinfunction "2_2") (pintype "passive"))
      (node (ref "J2") (pin "19") (pinfunction "19_19") (pintype "bidirectional"))
    )
    (net (code "29") (name "Net-(EPD_C8-Pad2)") (class "Default")
      (node (ref "EPD_C8") (pin "2") (pinfunction "2_2") (pintype "passive"))
      (node (ref "J2") (pin "20") (pinfunction "20_20") (pintype "bidirectional"))
    )
    (net (code "30") (name "Net-(EPD_C9-Pad2)") (class "Default")
      (node (ref "EPD_C9") (pin "2") (pinfunction "2_2") (pintype "passive"))
      (node (ref "J2") (pin "21") (pinfunction "21_21") (pintype "bidirectional"))
    )
    (net (code "31") (name "Net-(EPD_C10-Pad2)") (class "Default")
      (node (ref "EPD_C10") (pin "2") (pinfunction "2_2") (pintype "passive"))
      (node (ref "J2") (pin "22") (pinfunction "22_22") (pintype "bidirectional"))
    )
    (net (code "32") (name "Net-(EPD_C11-Pad2)") (class "Default")
      (node (ref "EPD_C11") (pin "2") (pinfunction "2_2") (pintype "passive"))
      (node (ref "J2") (pin "23") (pinfunction "23_23") (pintype "bidirectional"))
    )
    (net (code "33") (name "Net-(EPD_C12-Pad2)") (class "Default")
      (node (ref "EPD_C12") (pin "2") (pinfunction "2_2") (pintype "passive"))
      (node (ref "J2") (pin "24") (pinfunction "24_24") (pintype "bidirectional"))
    )
    (net (code "34") (name "Net-(IC1-CT)") (class "Default")
      (node (ref "C_DELAY") (pin "1") (pinfunction "1_1") (pintype "passive"))
      (node (ref "IC1") (pin "5") (pinfunction "CT_5") (pintype "bidirectional"))
    )
    (net (code "35") (name "Net-(J1-PadA5)") (class "Default")
      (node (ref "J1") (pin "A5") (pinfunction "A5_A5") (pintype "bidirectional"))
      (node (ref "R2-USB1") (pin "2") (pinfunction "2_2") (pintype "passive"))
    )
    (net (code "36") (name "Net-(J1-PadB5)") (class "Default")
      (node (ref "J1") (pin "B5") (pinfunction "B5_B5") (pintype "bidirectional"))
      (node (ref "R2-USB") (pin "1") (pinfunction "1_1") (pintype "passive"))
    )
    (net (code "37") (name "Net-(MCP73831-PROG)") (class "Default")
      (node (ref "MCP73831") (pin "5") (pinfunction "PROG_5") (pintype "input"))
      (node (ref "R2_BAT") (pin "2") (pinfunction "2_2") (pintype "passive"))
    )
    (net (code "38") (name "Net-(MCP73831-STAT)") (class "Default")
      (node (ref "MCP73831") (pin "1") (pinfunction "STAT_1") (pintype "output"))
      (node (ref "R1_BAT") (pin "2") (pinfunction "2_2") (pintype "passive"))
    )
    (net (code "39") (name "PREVGH") (class "Default")
      (node (ref "D5") (pin "1") (pinfunction "K_1") (pintype "bidirectional"))
    )
    (net (code "40") (name "PREVGL") (class "Default")
      (node (ref "D4") (pin "2") (pinfunction "A_2") (pintype "bidirectional"))
    )
    (net (code "41") (name "RESE") (class "Default")
      (node (ref "J2") (pin "3") (pinfunction "3_3") (pintype "bidirectional"))
      (node (ref "Q3") (pin "2") (pinfunction "S_2") (pintype "bidirectional"))
      (node (ref "R3") (pin "2") (pinfunction "2_2") (pintype "passive"))
    )
    (net (code "42") (name "RESE'") (class "Default")
      (node (ref "R1") (pin "2") (pinfunction "2_2") (pintype "passive"))
      (node (ref "R3") (pin "1") (pinfunction "1_1") (pintype "passive"))
      (node (ref "SJ1") (pin "2") (pinfunction "2_2") (pintype "passive"))
    )
    (net (code "43") (name "RESET") (class "Default")
      (node (ref "C5") (pin "1") (pinfunction "1_1") (pintype "passive"))
      (node (ref "IC1") (pin "1") (pinfunction "VOUT_1") (pintype "bidirectional"))
      (node (ref "RESET_BUTTON") (pin "3") (pinfunction "3_3") (pintype "passive"))
      (node (ref "RESET_BUTTON") (pin "4") (pinfunction "4_4") (pintype "passive"))
      (node (ref "R_RESET") (pin "1") (pinfunction "1_1") (pintype "passive"))
      (node (ref "U2") (pin "3") (pinfunction "EN_3") (pintype "input"))
    )
    (net (code "44") (name "RTC_RST") (class "Default")
      (node (ref "U2") (pin "16") (pinfunction "IO18_16") (pintype "bidirectional"))
      (node (ref "U3") (pin "4") (pinfunction "~{RST}_4") (pintype "input"))
    )
    (net (code "45") (name "RX") (class "Default")
      (node (ref "TP2") (pin "TP") (pinfunction "TP_TP") (pintype "input"))
      (node (ref "U2") (pin "24") (pinfunction "RXD0/GPIO17_24") (pintype "bidirectional"))
    )
    (net (code "46") (name "SCK") (class "Default")
      (node (ref "D10") (pin "2") (pinfunction "2_2") (pintype "passive"))
      (node (ref "J2") (pin "13") (pinfunction "13_13") (pintype "bidirectional"))
      (node (ref "J4") (pin "P5") (pinfunction "CLK_P5") (pintype "bidirectional"))
      (node (ref "R6") (pin "1") (pinfunction "1_1") (pintype "passive"))
      (node (ref "TP8") (pin "TP") (pinfunction "TP_TP") (pintype "input"))
      (node (ref "U1") (pin "6") (pinfunction "CLK_6") (pintype "input"))
      (node (ref "U2") (pin "6") (pinfunction "IO6_6") (pintype "bidirectional"))
    )
    (net (code "47") (name "SCL") (class "Default")
      (node (ref "J3") (pin "4") (pinfunction "4_4") (pintype "passive"))
      (node (ref "R2-PINH") (pin "1") (pinfunction "1_1") (pintype "passive"))
      (node (ref "SENSOR2") (pin "4") (pinfunction "SCK_4") (pintype "input"))
      (node (ref "U2") (pin "20") (pinfunction "IO22_20") (pintype "bidirectional"))
      (node (ref "U3") (pin "16") (pinfunction "SCL_16") (pintype "input"))
      (node (ref "U4") (pin "7") (pinfunction "SCL_7") (pintype "input"))
    )
    (net (code "48") (name "SDA") (class "Default")
      (node (ref "J3") (pin "3") (pinfunction "3_3") (pintype "passive"))
      (node (ref "R1_PINH") (pin "1") (pinfunction "1_1") (pintype "passive"))
      (node (ref "SENSOR2") (pin "3") (pinfunction "SDI_3") (pintype "bidirectional"))
      (node (ref "U2") (pin "19") (pinfunction "IO21_19") (pintype "bidirectional"))
      (node (ref "U3") (pin "15") (pinfunction "SDA_15") (pintype "bidirectional"))
      (node (ref "U4") (pin "8") (pinfunction "SDA_8") (pintype "bidirectional"))
    )
    (net (code "49") (name "SRC") (class "Default")
      (node (ref "C4") (pin "2") (pinfunction "2_2") (pintype "passive"))
      (node (ref "D5") (pin "2") (pinfunction "A_2") (pintype "bidirectional"))
      (node (ref "L1") (pin "1") (pinfunction "1_1") (pintype "passive"))
      (node (ref "Q3") (pin "3") (pinfunction "D_3") (pintype "bidirectional"))
    )
    (net (code "50") (name "SS_SD") (class "Default")
      (node (ref "D8") (pin "2") (pinfunction "2_2") (pintype "passive"))
      (node (ref "J4") (pin "P2") (pinfunction "CD/DAT3_P2") (pintype "bidirectional"))
      (node (ref "R10") (pin "1") (pinfunction "1_1") (pintype "passive"))
      (node (ref "U2") (pin "4") (pinfunction "IO4_4") (pintype "bidirectional"))
    )
    (net (code "51") (name "TX") (class "Default")
      (node (ref "TP1") (pin "TP") (pinfunction "TP_TP") (pintype "input"))
      (node (ref "U2") (pin "25") (pinfunction "TXD0/GPIO16_25") (pintype "bidirectional"))
    )
    (net (code "52") (name "USB_D+") (class "Default")
      (node (ref "D1") (pin "1") (pinfunction "I/O1_1_1") (pintype "bidirectional"))
      (node (ref "U2") (pin "14") (pinfunction "IO13_14") (pintype "bidirectional"))
    )
    (net (code "53") (name "USB_D-") (class "Default")
      (node (ref "D1") (pin "3") (pinfunction "I/O2_1_3") (pintype "bidirectional"))
      (node (ref "U2") (pin "13") (pinfunction "IO12_13") (pintype "bidirectional"))
    )
    (net (code "54") (name "VBAT") (class "Default")
      (node (ref "C2_BAT") (pin "1") (pinfunction "1_1") (pintype "passive"))
      (node (ref "MCP73831") (pin "3") (pinfunction "VBAT_3") (pintype "power_in"))
      (node (ref "Q1") (pin "3") (pinfunction "D_3") (pintype "bidirectional"))
      (node (ref "TP3") (pin "TP") (pinfunction "TP_TP") (pintype "input"))
      (node (ref "U4") (pin "2") (pinfunction "CELL_2") (pintype "power_in"))
      (node (ref "U4") (pin "3") (pinfunction "VDD_3") (pintype "power_in"))
    )
    (net (code "55") (name "VBUS") (class "Default")
      (node (ref "C1_BAT") (pin "1") (pinfunction "1_1") (pintype "passive"))
      (node (ref "C4_USB") (pin "1") (pinfunction "1_1") (pintype "passive"))
      (node (ref "C5_USB") (pin "1") (pinfunction "1_1") (pintype "passive"))
      (node (ref "CHG_LED") (pin "A") (pinfunction "A_A") (pintype "passive"))
      (node (ref "D1") (pin "5") (pinfunction "VBUS_5") (pintype "bidirectional"))
      (node (ref "D2") (pin "2") (pinfunction "ANODE_2") (pintype "bidirectional"))
      (node (ref "MCP73831") (pin "4") (pinfunction "VIN_4") (pintype "power_in"))
      (node (ref "PFMF.050.1") (pin "2") (pinfunction "2_2") (pintype "passive"))
      (node (ref "Q1") (pin "1") (pinfunction "G_1") (pintype "bidirectional"))
      (node (ref "R1_PWRUSB") (pin "2") (pinfunction "2_2") (pintype "passive"))
      (node (ref "TP14") (pin "TP") (pinfunction "TP_TP") (pintype "input"))
    )
    (net (code "56") (name "VRTC") (class "Default")
      (node (ref "C10_SUPERCAP") (pin "2") (pinfunction "2_2") (pintype "passive"))
      (node (ref "C8") (pin "1") (pinfunction "1_1") (pintype "passive"))
      (node (ref "R_CAPACITOR") (pin "2") (pinfunction "2_2") (pintype "passive"))
      (node (ref "U3") (pin "14") (pinfunction "VBAT_14") (pintype "power_in"))
    )
    (net (code "57") (name "VUSB") (class "Default")
      (node (ref "J1") (pin "A4") (pinfunction "A4_A4") (pintype "bidirectional"))
      (node (ref "J1") (pin "A9") (pinfunction "A9_A9") (pintype "bidirectional"))
      (node (ref "J1") (pin "B4") (pinfunction "B4_B4") (pintype "bidirectional"))
      (node (ref "J1") (pin "B9") (pinfunction "B9_B9") (pintype "bidirectional"))
      (node (ref "PFMF.050.1") (pin "1") (pinfunction "1_1") (pintype "passive"))
    )
    (net (code "58") (name "unconnected-(IC1-NC-Pad4)") (class "Default")
      (node (ref "IC1") (pin "4") (pinfunction "NC_4") (pintype "no_connect"))
    )
    (net (code "59") (name "unconnected-(IC4-NC-Pad4)") (class "Default")
      (node (ref "IC4") (pin "4") (pinfunction "NC_4") (pintype "no_connect"))
    )
    (net (code "60") (name "unconnected-(J1-PadA8)") (class "Default")
      (node (ref "J1") (pin "A8") (pinfunction "A8_A8") (pintype "bidirectional"))
    )
    (net (code "61") (name "unconnected-(J1-PadB8)") (class "Default")
      (node (ref "J1") (pin "B8") (pinfunction "B8_B8") (pintype "bidirectional"))
    )
    (net (code "62") (name "unconnected-(J2-Pad1)") (class "Default")
      (node (ref "J2") (pin "1") (pinfunction "1_1") (pintype "bidirectional"))
    )
    (net (code "63") (name "unconnected-(J2-Pad6)") (class "Default")
      (node (ref "J2") (pin "6") (pinfunction "6_6") (pintype "bidirectional"))
    )
    (net (code "64") (name "unconnected-(J2-Pad7)") (class "Default")
      (node (ref "J2") (pin "7") (pinfunction "7_7") (pintype "bidirectional"))
    )
    (net (code "65") (name "unconnected-(J4-DAT1-PadP8)") (class "Default")
      (node (ref "J4") (pin "P8") (pinfunction "DAT1_P8") (pintype "bidirectional"))
    )
    (net (code "66") (name "unconnected-(J4-DAT2-PadP1)") (class "Default")
      (node (ref "J4") (pin "P1") (pinfunction "DAT2_P1") (pintype "bidirectional"))
    )
    (net (code "67") (name "unconnected-(J4-DETECTION_1-PadS1)") (class "Default")
      (node (ref "J4") (pin "S1") (pinfunction "DETECTION_1_S1") (pintype "bidirectional"))
    )
    (net (code "68") (name "unconnected-(J4-DETECTION_2-PadS2)") (class "Default")
      (node (ref "J4") (pin "S2") (pinfunction "DETECTION_2_S2") (pintype "bidirectional"))
    )
    (net (code "69") (name "unconnected-(U2-NC-Pad22)") (class "Default")
      (node (ref "U2") (pin "22") (pinfunction "NC_22") (pintype "no_connect"))
    )
    (net (code "70") (name "unconnected-(U4-~{ALERT}-Pad5)") (class "Default")
      (node (ref "U4") (pin "5") (pinfunction "~{ALERT}_5") (pintype "output"))
    )
  )
)
